# 8LEDs.net
KiCad netlist of a schematic drawn in EAGLE
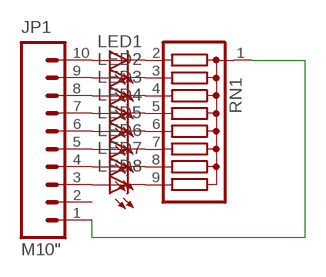
[diagram p0: schematic, sheet 1]

(export (version "E")
  (design (tool "Eeschema 10.0.6"))
  (components
    (comp (ref "JP1")
      (value "M10\"")
      (footprint "eagle-import:1X10")
      (libsource (lib "eagle-import") (part "M10{dblquote}"))
    )
    (comp (ref "LED1")
      (value "LED5MM")
      (footprint "eagle-import:LED5MM")
      (libsource (lib "eagle-import") (part "LED5MM"))
    )
    (comp (ref "LED2")
      (value "LED5MM")
      (footprint "eagle-import:LED5MM")
      (libsource (lib "eagle-import") (part "LED5MM"))
    )
    (comp (ref "LED3")
      (value "LED5MM")
      (footprint "eagle-import:LED5MM")
      (libsource (lib "eagle-import") (part "LED5MM"))
    )
    (comp (ref "LED4")
      (value "LED5MM")
      (footprint "eagle-import:LED5MM")
      (libsource (lib "eagle-import") (part "LED5MM"))
    )
    (comp (ref "LED5")
      (value "LED5MM")
      (footprint "eagle-import:LED5MM")
      (libsource (lib "eagle-import") (part "LED5MM"))
    )
    (comp (ref "LED6")
      (value "LED5MM")
      (footprint "eagle-import:LED5MM")
      (libsource (lib "eagle-import") (part "LED5MM"))
    )
    (comp (ref "LED7")
      (value "LED5MM")
      (footprint "eagle-import:LED5MM")
      (libsource (lib "eagle-import") (part "LED5MM"))
    )
    (comp (ref "LED8")
      (value "LED5MM")
      (footprint "eagle-import:LED5MM")
      (libsource (lib "eagle-import") (part "LED5MM"))
    )
    (comp (ref "RN1")
      (value "G08R")
      (footprint "eagle-import:SIL9")
      (libsource (lib "eagle-import") (part "G08R"))
    )
  )
  (nets
    (net (code "1") (name "Net-(JP1-Pad1)") (class "Default")
      (node (ref "JP1") (pin "1") (pinfunction "1_1") (pintype "passive"))
      (node (ref "RN1") (pin "1") (pinfunction "1_1") (pintype "passive"))
    )
    (net (code "2") (name "Net-(JP1-Pad3)") (class "Default")
      (node (ref "JP1") (pin "3") (pinfunction "3_3") (pintype "passive"))
      (node (ref "LED8") (pin "A") (pinfunction "A_A") (pintype "passive"))
    )
    (net (code "3") (name "Net-(JP1-Pad4)") (class "Default")
      (node (ref "JP1") (pin "4") (pinfunction "4_4") (pintype "passive"))
      (node (ref "LED7") (pin "A") (pinfunction "A_A") (pintype "passive"))
    )
    (net (code "4") (name "Net-(JP1-Pad5)") (class "Default")
      (node (ref "JP1") (pin "5") (pinfunction "5_5") (pintype "passive"))
      (node (ref "LED6") (pin "A") (pinfunction "A_A") (pintype "passive"))
    )
    (net (code "5") (name "Net-(JP1-Pad6)") (class "Default")
      (node (ref "JP1") (pin "6") (pinfunction "6_6") (pintype "passive"))
      (node (ref "LED5") (pin "A") (pinfunction "A_A") (pintype "passive"))
    )
    (net (code "6") (name "Net-(JP1-Pad7)") (class "Default")
      (node (ref "JP1") (pin "7") (pinfunction "7_7") (pintype "passive"))
      (node (ref "LED4") (pin "A") (pinfunction "A_A") (pintype "passive"))
    )
    (net (code "7") (name "Net-(JP1-Pad8)") (class "Default")
      (node (ref "JP1") (pin "8") (pinfunction "8_8") (pintype "passive"))
      (node (ref "LED3") (pin "A") (pinfunction "A_A") (pintype "passive"))
    )
    (net (code "8") (name "Net-(JP1-Pad9)") (class "Default")
      (node (ref "JP1") (pin "9") (pinfunction "9_9") (pintype "passive"))
      (node (ref "LED2") (pin "A") (pinfunction "A_A") (pintype "passive"))
    )
    (net (code "9") (name "Net-(JP1-Pad10)") (class "Default")
      (node (ref "JP1") (pin "10") (pinfunction "10_10") (pintype "passive"))
      (node (ref "LED1") (pin "A") (pinfunction "A_A") (pintype "passive"))
    )
    (net (code "10") (name "Net-(LED1-C)") (class "Default")
      (node (ref "LED1") (pin "K") (pinfunction "C_K") (pintype "passive"))
      (node (ref "RN1") (pin "2") (pinfunction "2_2") (pintype "passive"))
    )
    (net (code "11") (name "Net-(LED2-C)") (class "Default")
      (node (ref "LED2") (pin "K") (pinfunction "C_K") (pintype "passive"))
      (node (ref "RN1") (pin "3") (pinfunction "3_3") (pintype "passive"))
    )
    (net (code "12") (name "Net-(LED3-C)") (class "Default")
      (node (ref "LED3") (pin "K") (pinfunction "C_K") (pintype "passive"))
      (node (ref "RN1") (pin "4") (pinfunction "4_4") (pintype "passive"))
    )
    (net (code "13") (name "Net-(LED4-C)") (class "Default")
      (node (ref "LED4") (pin "K") (pinfunction "C_K") (pintype "passive"))
      (node (ref "RN1") (pin "5") (pinfunction "5_5") (pintype "passive"))
    )
    (net (code "14") (name "Net-(LED5-C)") (class "Default")
      (node (ref "LED5") (pin "K") (pinfunction "C_K") (pintype "passive"))
      (node (ref "RN1") (pin "6") (pinfunction "6_6") (pintype "passive"))
    )
    (net (code "15") (name "Net-(LED6-C)") (class "Default")
      (node (ref "LED6") (pin "K") (pinfunction "C_K") (pintype "passive"))
      (node (ref "RN1") (pin "7") (pinfunction "7_7") (pintype "passive"))
    )
    (net (code "16") (name "Net-(LED7-C)") (class "Default")
      (node (ref "LED7") (pin "K") (pinfunction "C_K") (pintype "passive"))
      (node (ref "RN1") (pin "8") (pinfunction "8_8") (pintype "passive"))
    )
    (net (code "17") (name "Net-(LED8-C)") (class "Default")
      (node (ref "LED8") (pin "K") (pinfunction "C_K") (pintype "passive"))
      (node (ref "RN1") (pin "9") (pinfunction "9_9") (pintype "passive"))
    )
    (net (code "18") (name "unconnected-(JP1-Pad2)") (class "Default")
      (node (ref "JP1") (pin "2") (pinfunction "2_2") (pintype "passive"))
    )
  )
)
